# LB_BIT_o24_SYNTHSPEAKER-v03_4_5.net
KiCad netlist of a schematic drawn in EAGLE
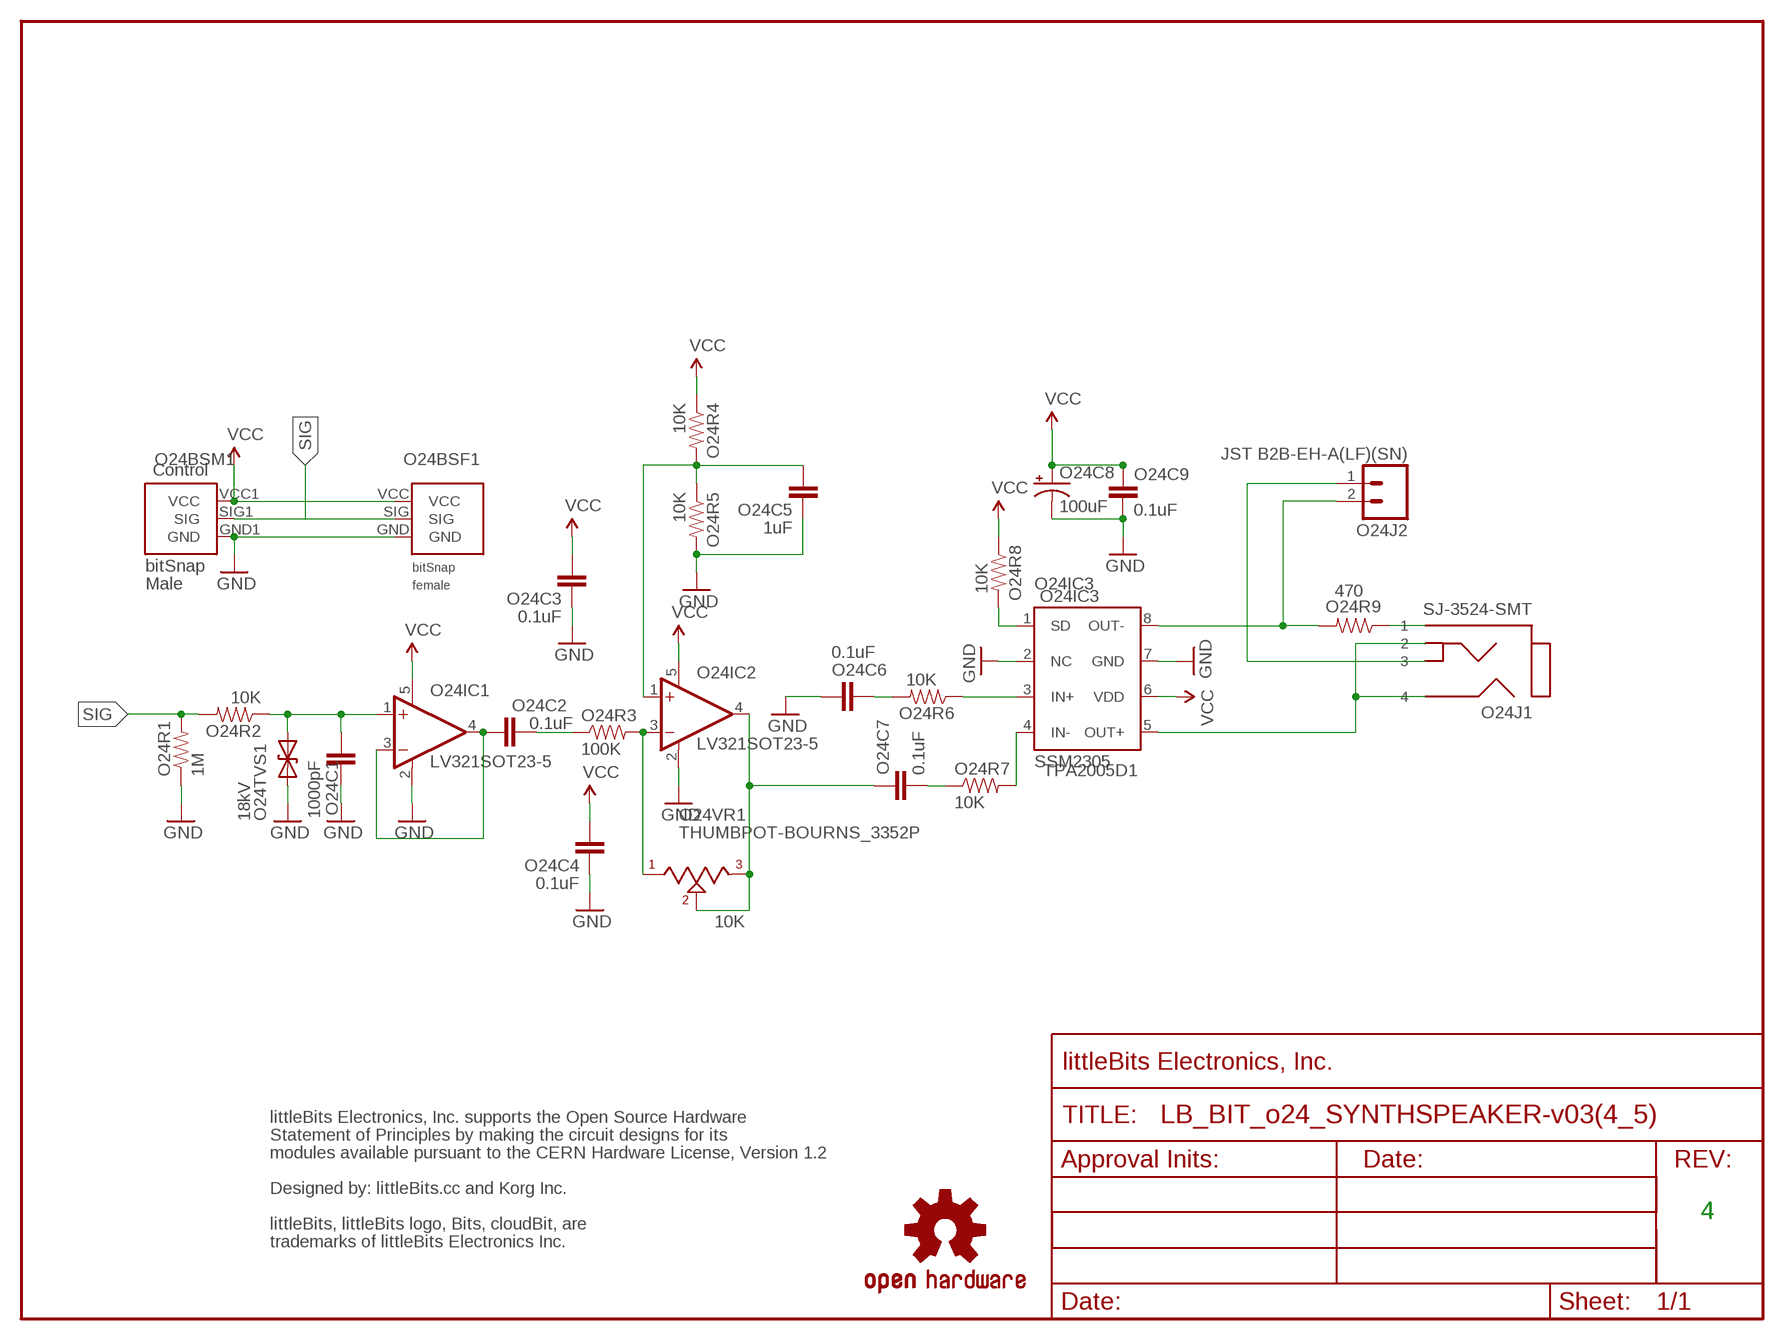
[diagram p0: schematic, sheet 1]

(export (version "E")
  (design (tool "Eeschema 10.0.6"))
  (components
    (comp (ref "$1_28_$")
      (value "OSHW-LOGOL")
      (footprint "eagle-import:OSHW-LOGO-L")
      (libsource (lib "eagle-import") (part "OSHW-LOGOL"))
    )
    (comp (ref "FRAME1")
      (value "FRAME-LETTER-OHWOHW")
      (footprint "eagle-import:FABDWG01-OHW")
      (libsource (lib "eagle-import") (part "FRAME-LETTER-OHWOHW"))
    )
    (comp (ref "O24BSF1")
      (value "BITSNAP_V03_FEMALE")
      (footprint "eagle-import:BITSNAP_V03_FEMALE")
      (libsource (lib "eagle-import") (part "BITSNAP_V03_FEMALE"))
    )
    (comp (ref "O24BSM1")
      (value "BITSNAP_V03_MALE")
      (footprint "eagle-import:BITSNAP_V03_MALE")
      (libsource (lib "eagle-import") (part "BITSNAP_V03_MALE"))
    )
    (comp (ref "O24C1")
      (value "1000pF")
      (footprint "eagle-import:CAP-0603")
      (libsource (lib "eagle-import") (part "CAPCAP-0603"))
    )
    (comp (ref "O24C2")
      (value "0.1uF")
      (footprint "eagle-import:CAP-0603")
      (libsource (lib "eagle-import") (part "CAPCAP-0603"))
    )
    (comp (ref "O24C3")
      (value "0.1uF")
      (footprint "eagle-import:CAP-0603")
      (libsource (lib "eagle-import") (part "CAPCAP-0603"))
    )
    (comp (ref "O24C4")
      (value "0.1uF")
      (footprint "eagle-import:CAP-0603")
      (libsource (lib "eagle-import") (part "CAPCAP-0603"))
    )
    (comp (ref "O24C5")
      (value "1uF")
      (footprint "eagle-import:CAP-0603")
      (libsource (lib "eagle-import") (part "CAPCAP-0603"))
    )
    (comp (ref "O24C6")
      (value "0.1uF")
      (footprint "eagle-import:CAP-0603")
      (libsource (lib "eagle-import") (part "CAPCAP-0603"))
    )
    (comp (ref "O24C7")
      (value "0.1uF")
      (footprint "eagle-import:CAP-0603")
      (libsource (lib "eagle-import") (part "CAPCAP-0603"))
    )
    (comp (ref "O24C8")
      (value "100uF")
      (footprint "eagle-import:EIA3216")
      (libsource (lib "eagle-import") (part "CAP_POL3216"))
    )
    (comp (ref "O24C9")
      (value "0.1uF")
      (footprint "eagle-import:CAP-0603")
      (libsource (lib "eagle-import") (part "CAPCAP-0603"))
    )
    (comp (ref "O24IC1")
      (value "LV321SOT23-5")
      (footprint "eagle-import:SOT23-5")
      (libsource (lib "eagle-import") (part "LV321SOT23-5"))
    )
    (comp (ref "O24IC2")
      (value "LV321SOT23-5")
      (footprint "eagle-import:SOT23-5")
      (libsource (lib "eagle-import") (part "LV321SOT23-5"))
    )
    (comp (ref "O24IC3")
      (value "SSM2305")
      (footprint "eagle-import:MSOP08")
      (libsource (lib "eagle-import") (part "SSM2305"))
    )
    (comp (ref "O24J1")
      (value "SJ-3524-SMT")
      (footprint "eagle-import:PHONO_JACK_SW")
      (libsource (lib "eagle-import") (part "PHONO_JACK_SW"))
    )
    (comp (ref "O24J2")
      (value "JST B2B-EH-A(LF)(SN)")
      (footprint "eagle-import:H02-JST-B2B-EH-A")
      (libsource (lib "eagle-import") (part "HDR-2"))
    )
    (comp (ref "O24R1")
      (value "1M")
      (footprint "eagle-import:RES-0603")
      (libsource (lib "eagle-import") (part "RESISTOR0603"))
    )
    (comp (ref "O24R2")
      (value "10K")
      (footprint "eagle-import:RES-0603")
      (libsource (lib "eagle-import") (part "RESISTOR0603"))
    )
    (comp (ref "O24R3")
      (value "100K")
      (footprint "eagle-import:RES-0603")
      (libsource (lib "eagle-import") (part "RESISTOR0603"))
    )
    (comp (ref "O24R4")
      (value "10K")
      (footprint "eagle-import:RES-0603")
      (libsource (lib "eagle-import") (part "RESISTOR0603"))
    )
    (comp (ref "O24R5")
      (value "10K")
      (footprint "eagle-import:RES-0603")
      (libsource (lib "eagle-import") (part "RESISTOR0603"))
    )
    (comp (ref "O24R6")
      (value "10K")
      (footprint "eagle-import:RES-0603")
      (libsource (lib "eagle-import") (part "RESISTOR0603"))
    )
    (comp (ref "O24R7")
      (value "10K")
      (footprint "eagle-import:RES-0603")
      (libsource (lib "eagle-import") (part "RESISTOR0603"))
    )
    (comp (ref "O24R8")
      (value "10K")
      (footprint "eagle-import:RES-0603")
      (libsource (lib "eagle-import") (part "RESISTOR0603"))
    )
    (comp (ref "O24R9")
      (value "470")
      (footprint "eagle-import:RES-0603")
      (libsource (lib "eagle-import") (part "RESISTOR0603"))
    )
    (comp (ref "O24TVS1")
      (value "18kV")
      (footprint "eagle-import:SOD-923")
      (fields (field (name "MPN") "ESD9B5.0ST5G"))
      (libsource (lib "eagle-import") (part "DIODE-TVSSOD-923"))
    )
    (comp (ref "O24VR1")
      (value "THUMBPOT-BOURNS_3352P")
      (footprint "eagle-import:THUMBPOT-BOURNS_3352")
      (libsource (lib "eagle-import") (part "THUMBPOT-BOURNS_3352P"))
    )
    (comp (ref "U$1")
      (value "OSHWCREDIT-KORG")
      (footprint "eagle-import:OSHWCREDIT-KORG")
      (libsource (lib "eagle-import") (part "OSHWCREDIT-KORG"))
    )
  )
  (nets
    (net (code "1") (name "GND") (class "Default")
      (node (ref "O24BSF1") (pin "GND") (pinfunction "GND_GND") (pintype "bidirectional"))
      (node (ref "O24BSM1") (pin "GND1") (pinfunction "GND_GND1") (pintype "bidirectional"))
      (node (ref "O24C1") (pin "1") (pinfunction "1_1") (pintype "passive"))
      (node (ref "O24C3") (pin "1") (pinfunction "1_1") (pintype "passive"))
      (node (ref "O24C4") (pin "1") (pinfunction "1_1") (pintype "passive"))
      (node (ref "O24C5") (pin "1") (pinfunction "1_1") (pintype "passive"))
      (node (ref "O24C6") (pin "2") (pinfunction "2_2") (pintype "passive"))
      (node (ref "O24C8") (pin "-") (pinfunction "-_-") (pintype "passive"))
      (node (ref "O24C9") (pin "2") (pinfunction "2_2") (pintype "passive"))
      (node (ref "O24IC1") (pin "2") (pinfunction "V-_2") (pintype "power_in"))
      (node (ref "O24IC2") (pin "2") (pinfunction "V-_2") (pintype "power_in"))
      (node (ref "O24IC3") (pin "2") (pinfunction "NC_2") (pintype "bidirectional"))
      (node (ref "O24IC3") (pin "7") (pinfunction "GND_7") (pintype "bidirectional"))
      (node (ref "O24R1") (pin "1") (pinfunction "1_1") (pintype "passive"))
      (node (ref "O24R5") (pin "2") (pinfunction "2_2") (pintype "passive"))
      (node (ref "O24TVS1") (pin "1") (pinfunction "A_1") (pintype "passive"))
    )
    (net (code "2") (name "Net-(O24C2-Pad1)") (class "Default")
      (node (ref "O24C2") (pin "1") (pinfunction "1_1") (pintype "passive"))
      (node (ref "O24R3") (pin "1") (pinfunction "1_1") (pintype "passive"))
    )
    (net (code "3") (name "Net-(O24C6-Pad1)") (class "Default")
      (node (ref "O24C6") (pin "1") (pinfunction "1_1") (pintype "passive"))
      (node (ref "O24R6") (pin "2") (pinfunction "2_2") (pintype "passive"))
    )
    (net (code "4") (name "Net-(O24C7-Pad2)") (class "Default")
      (node (ref "O24C7") (pin "2") (pinfunction "2_2") (pintype "passive"))
      (node (ref "O24R7") (pin "1") (pinfunction "1_1") (pintype "passive"))
    )
    (net (code "5") (name "Net-(O24IC1-+IN)") (class "Default")
      (node (ref "O24C1") (pin "2") (pinfunction "2_2") (pintype "passive"))
      (node (ref "O24IC1") (pin "1") (pinfunction "+IN_1") (pintype "input"))
      (node (ref "O24R2") (pin "1") (pinfunction "1_1") (pintype "passive"))
      (node (ref "O24TVS1") (pin "2") (pinfunction "C_2") (pintype "passive"))
    )
    (net (code "6") (name "Net-(O24IC1--IN)") (class "Default")
      (node (ref "O24C2") (pin "2") (pinfunction "2_2") (pintype "passive"))
      (node (ref "O24IC1") (pin "3") (pinfunction "-IN_3") (pintype "input"))
      (node (ref "O24IC1") (pin "4") (pinfunction "OUT_4") (pintype "output"))
    )
    (net (code "7") (name "Net-(O24IC2-+IN)") (class "Default")
      (node (ref "O24C5") (pin "2") (pinfunction "2_2") (pintype "passive"))
      (node (ref "O24IC2") (pin "1") (pinfunction "+IN_1") (pintype "input"))
      (node (ref "O24R4") (pin "2") (pinfunction "2_2") (pintype "passive"))
      (node (ref "O24R5") (pin "1") (pinfunction "1_1") (pintype "passive"))
    )
    (net (code "8") (name "Net-(O24IC2--IN)") (class "Default")
      (node (ref "O24IC2") (pin "3") (pinfunction "-IN_3") (pintype "input"))
      (node (ref "O24R3") (pin "2") (pinfunction "2_2") (pintype "passive"))
      (node (ref "O24VR1") (pin "3") (pinfunction "1_3") (pintype "passive"))
    )
    (net (code "9") (name "Net-(O24IC2-OUT)") (class "Default")
      (node (ref "O24C7") (pin "1") (pinfunction "1_1") (pintype "passive"))
      (node (ref "O24IC2") (pin "4") (pinfunction "OUT_4") (pintype "output"))
      (node (ref "O24VR1") (pin "1") (pinfunction "3_1") (pintype "passive"))
      (node (ref "O24VR1") (pin "2") (pinfunction "2_2") (pintype "passive"))
    )
    (net (code "10") (name "Net-(O24IC3-IN+)") (class "Default")
      (node (ref "O24IC3") (pin "3") (pinfunction "IN+_3") (pintype "bidirectional"))
      (node (ref "O24R6") (pin "1") (pinfunction "1_1") (pintype "passive"))
    )
    (net (code "11") (name "Net-(O24IC3-IN-)") (class "Default")
      (node (ref "O24IC3") (pin "4") (pinfunction "IN-_4") (pintype "bidirectional"))
      (node (ref "O24R7") (pin "2") (pinfunction "2_2") (pintype "passive"))
    )
    (net (code "12") (name "Net-(O24IC3-OUT+)") (class "Default")
      (node (ref "O24IC3") (pin "5") (pinfunction "OUT+_5") (pintype "bidirectional"))
      (node (ref "O24J1") (pin "2") (pinfunction "2_2") (pintype "bidirectional"))
      (node (ref "O24J1") (pin "4") (pinfunction "4_4") (pintype "bidirectional"))
    )
    (net (code "13") (name "Net-(O24IC3-OUT-)") (class "Default")
      (node (ref "O24IC3") (pin "8") (pinfunction "OUT-_8") (pintype "bidirectional"))
      (node (ref "O24J2") (pin "2") (pinfunction "2_2") (pintype "passive"))
      (node (ref "O24R9") (pin "2") (pinfunction "2_2") (pintype "passive"))
    )
    (net (code "14") (name "Net-(O24IC3-SD)") (class "Default")
      (node (ref "O24IC3") (pin "1") (pinfunction "SD_1") (pintype "bidirectional"))
      (node (ref "O24R8") (pin "2") (pinfunction "2_2") (pintype "passive"))
    )
    (net (code "15") (name "Net-(O24J1-Pad1)") (class "Default")
      (node (ref "O24J1") (pin "1") (pinfunction "1_1") (pintype "bidirectional"))
      (node (ref "O24R9") (pin "1") (pinfunction "1_1") (pintype "passive"))
    )
    (net (code "16") (name "Net-(O24J1-Pad3)") (class "Default")
      (node (ref "O24J1") (pin "3") (pinfunction "3_3") (pintype "bidirectional"))
      (node (ref "O24J2") (pin "1") (pinfunction "1_1") (pintype "passive"))
    )
    (net (code "17") (name "SIG") (class "Default")
      (node (ref "O24BSF1") (pin "SIG") (pinfunction "SIG_SIG") (pintype "bidirectional"))
      (node (ref "O24BSM1") (pin "SIG1") (pinfunction "SIG_SIG1") (pintype "bidirectional"))
      (node (ref "O24R1") (pin "2") (pinfunction "2_2") (pintype "passive"))
      (node (ref "O24R2") (pin "2") (pinfunction "2_2") (pintype "passive"))
    )
    (net (code "18") (name "VCC") (class "Default")
      (node (ref "O24BSF1") (pin "VCC") (pinfunction "VCC_VCC") (pintype "bidirectional"))
      (node (ref "O24BSM1") (pin "VCC1") (pinfunction "VCC_VCC1") (pintype "bidirectional"))
      (node (ref "O24C3") (pin "2") (pinfunction "2_2") (pintype "passive"))
      (node (ref "O24C4") (pin "2") (pinfunction "2_2") (pintype "passive"))
      (node (ref "O24C8") (pin "+") (pinfunction "+_+") (pintype "passive"))
      (node (ref "O24C9") (pin "1") (pinfunction "1_1") (pintype "passive"))
      (node (ref "O24IC1") (pin "5") (pinfunction "V+_5") (pintype "power_in"))
      (node (ref "O24IC2") (pin "5") (pinfunction "V+_5") (pintype "power_in"))
      (node (ref "O24IC3") (pin "6") (pinfunction "VDD_6") (pintype "bidirectional"))
      (node (ref "O24R4") (pin "1") (pinfunction "1_1") (pintype "passive"))
      (node (ref "O24R8") (pin "1") (pinfunction "1_1") (pintype "passive"))
    )
  )
)
